# Fujin_Peripherals.net
KiCad netlist of a schematic drawn in Altium Designer
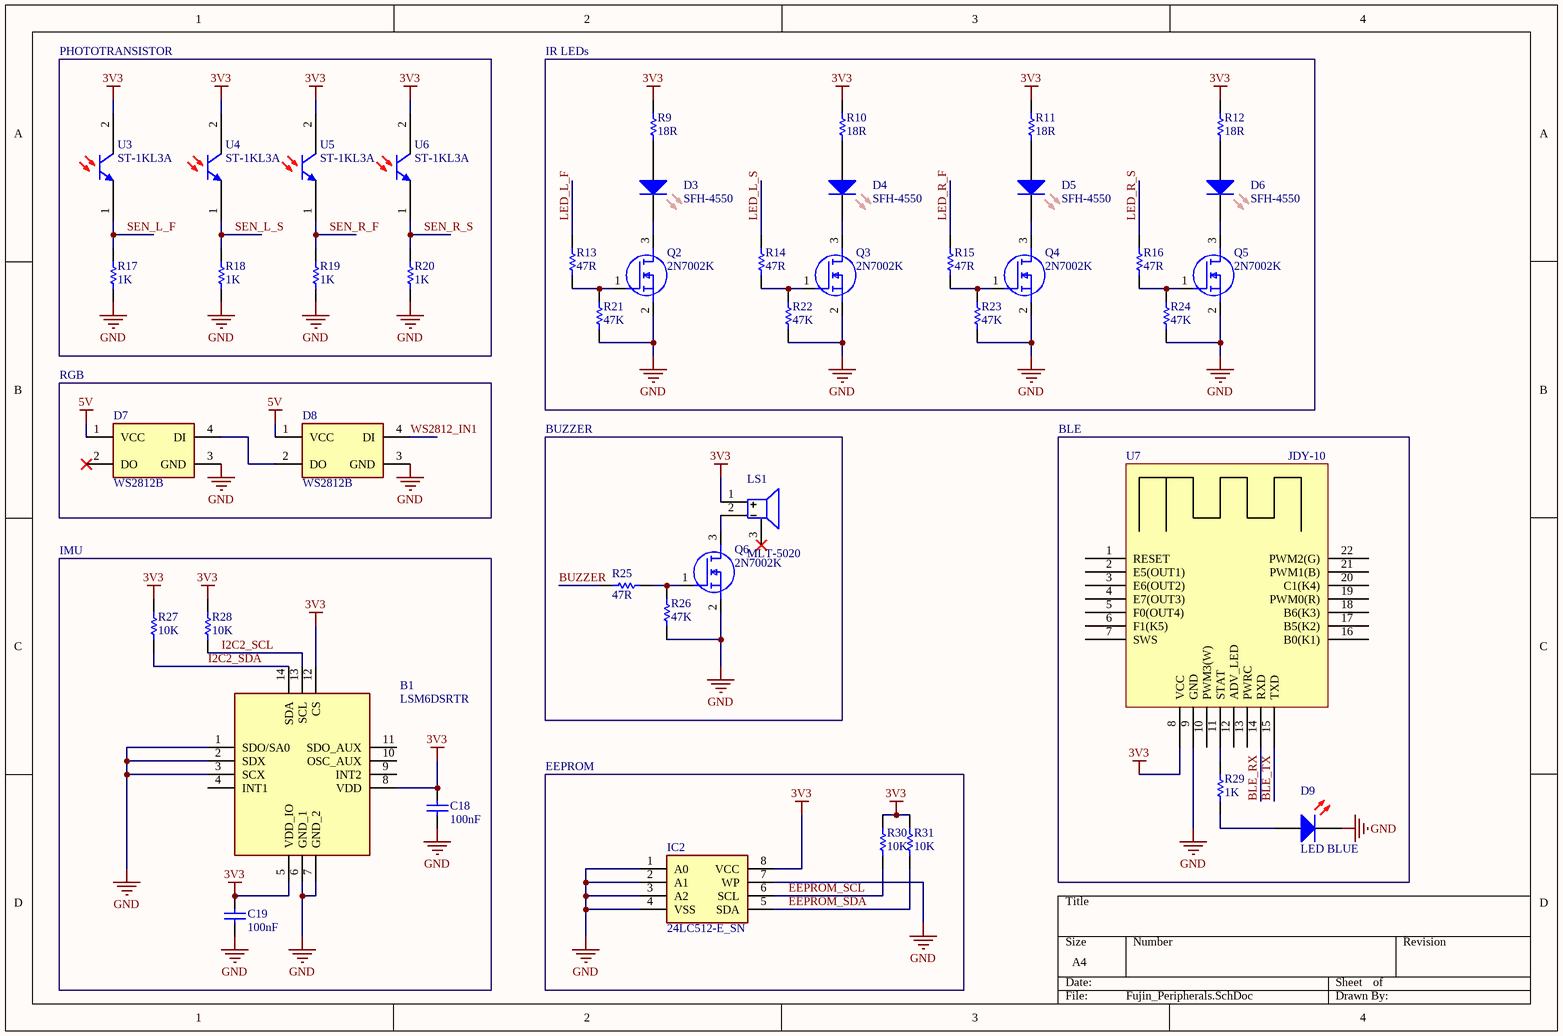
[diagram p0: Fujin_Peripherals.SchDoc]

(export (version "E")
  (design (tool "Eeschema 10.0.6"))
  (components
    (comp (ref "B1")
      (value "LSM6DSRTR")
      (footprint "QFN50P300X250X86-14N")
      (description "IMUs - Inertial Measurement Units")
      (libsource (lib "FujinLib") (part "LSM6DSRTR"))
    )
    (comp (ref "C18")
      (value "100nF")
      (footprint "CAP 0402")
      (description "Capacitor Cer 100nF 50V 0402")
      (fields (field (name "MANUFACTURER PART NUMBER") "IMP14925"))
      (libsource (lib "FujinLib") (part "CAP 100NF 50V 0402"))
    )
    (comp (ref "C19")
      (value "100nF")
      (footprint "CAP 0402")
      (description "Capacitor Cer 100nF 50V 0402")
      (fields (field (name "MANUFACTURER PART NUMBER") "IMP14925"))
      (libsource (lib "FujinLib") (part "CAP 100NF 50V 0402"))
    )
    (comp (ref "D3")
      (value "SFH-4550")
      (footprint "SFH-4550")
      (description "LED 5mm IR")
      (fields (field (name "MANUFACTURER") "OSRAM"))
      (libsource (lib "FujinLib") (part "SFH-4550"))
    )
    (comp (ref "D4")
      (value "SFH-4550")
      (footprint "SFH-4550")
      (description "LED 5mm IR")
      (fields (field (name "MANUFACTURER") "OSRAM"))
      (libsource (lib "FujinLib") (part "SFH-4550"))
    )
    (comp (ref "D5")
      (value "SFH-4550")
      (footprint "SFH-4550")
      (description "LED 5mm IR")
      (fields (field (name "MANUFACTURER") "OSRAM"))
      (libsource (lib "FujinLib") (part "SFH-4550"))
    )
    (comp (ref "D6")
      (value "SFH-4550")
      (footprint "SFH-4550")
      (description "LED 5mm IR")
      (fields (field (name "MANUFACTURER") "OSRAM"))
      (libsource (lib "FujinLib") (part "SFH-4550"))
    )
    (comp (ref "D7")
      (value "WS2812B")
      (footprint "WS2812B")
      (description "Diode")
      (fields (field (name "MANUFACTURER_PART_NUMBER") "WS2812"))
      (libsource (lib "FujinLib") (part "WS2812B"))
    )
    (comp (ref "D8")
      (value "WS2812B")
      (footprint "WS2812B")
      (description "Diode")
      (fields (field (name "MANUFACTURER_PART_NUMBER") "WS2812"))
      (libsource (lib "FujinLib") (part "WS2812B"))
    )
    (comp (ref "D9")
      (value "LED BLUE")
      (footprint "LED 0603")
      (description "LED")
      (fields
        (field (name "MANUFACTURER_PART_NUMBER") "SML-D12U1WT86")
        (field (name "MOUSER PART NUMBER") "755-SML-D12U1WT86")
      )
      (libsource (lib "FujinLib") (part "LED RED 0603"))
    )
    (comp (ref "IC2")
      (value "24LC512-E_SN")
      (footprint "SamacSys:SOIC127P600X175-8N")
      (description "Integrated Circuit")
      (fields
        (field (name "MANUFACTURER_PART_NUMBER") "24LC512-E/SN")
        (field (name "MOUSER PART NUMBER") "579-24LC512-E/SN")
      )
      (libsource (lib "FujinLib") (part "24LC512-E_SN"))
    )
    (comp (ref "LS1")
      (value "MLT-5020")
      (footprint "MLT-5020")
      (description "Loudspeaker or Buzzer")
      (fields
        (field (name "MANUFACTURER_PART_NUMBER") "SMT-0540-S-R")
        (field (name "MOUSER PART NUMBER") "665-SMT0540SR")
      )
      (libsource (lib "FujinLib") (part "MLT-5020"))
    )
    (comp (ref "Q2")
      (value "2N7002K")
      (footprint "SOT95P240X120-3N")
      (description "MOSFET (N-Channel)")
      (fields (field (name "MOUSER PART NUMBER") "512-2N7002K"))
      (libsource (lib "FujinLib") (part "2N7002K"))
    )
    (comp (ref "Q3")
      (value "2N7002K")
      (footprint "SOT95P240X120-3N")
      (description "MOSFET (N-Channel)")
      (fields (field (name "MOUSER PART NUMBER") "512-2N7002K"))
      (libsource (lib "FujinLib") (part "2N7002K"))
    )
    (comp (ref "Q4")
      (value "2N7002K")
      (footprint "SOT95P240X120-3N")
      (description "MOSFET (N-Channel)")
      (fields (field (name "MOUSER PART NUMBER") "512-2N7002K"))
      (libsource (lib "FujinLib") (part "2N7002K"))
    )
    (comp (ref "Q5")
      (value "2N7002K")
      (footprint "SOT95P240X120-3N")
      (description "MOSFET (N-Channel)")
      (fields (field (name "MOUSER PART NUMBER") "512-2N7002K"))
      (libsource (lib "FujinLib") (part "2N7002K"))
    )
    (comp (ref "Q6")
      (value "2N7002K")
      (footprint "SOT95P240X120-3N")
      (description "MOSFET (N-Channel)")
      (fields (field (name "MOUSER PART NUMBER") "512-2N7002K"))
      (libsource (lib "FujinLib") (part "2N7002K"))
    )
    (comp (ref "R9")
      (value "18R")
      (footprint "RESISTOR 0603")
      (fields
        (field (name "MANUFACTURER") "Ty-Ohm")
        (field (name "MANUFACTURER PART NUMBER") "CR25")
        (field (name "TOLERANCE") "±5%")
      )
      (libsource (lib "FujinLib") (part "RES 18R 5%"))
    )
    (comp (ref "R10")
      (value "18R")
      (footprint "RESISTOR 0603")
      (fields
        (field (name "MANUFACTURER") "Ty-Ohm")
        (field (name "MANUFACTURER PART NUMBER") "CR25")
        (field (name "TOLERANCE") "±5%")
      )
      (libsource (lib "FujinLib") (part "RES 18R 5%"))
    )
    (comp (ref "R11")
      (value "18R")
      (footprint "RESISTOR 0603")
      (fields
        (field (name "MANUFACTURER") "Ty-Ohm")
        (field (name "MANUFACTURER PART NUMBER") "CR25")
        (field (name "TOLERANCE") "±5%")
      )
      (libsource (lib "FujinLib") (part "RES 18R 5%"))
    )
    (comp (ref "R12")
      (value "18R")
      (footprint "RESISTOR 0603")
      (fields
        (field (name "MANUFACTURER") "Ty-Ohm")
        (field (name "MANUFACTURER PART NUMBER") "CR25")
        (field (name "TOLERANCE") "±5%")
      )
      (libsource (lib "FujinLib") (part "RES 18R 5%"))
    )
    (comp (ref "R13")
      (value "47R")
      (footprint "RESISTOR 0603")
      (fields
        (field (name "MANUFACTURER") "Ty-Ohm")
        (field (name "MANUFACTURER PART NUMBER") "CR25")
        (field (name "TOLERANCE") "±5%")
      )
      (libsource (lib "FujinLib") (part "RES 47R 5%"))
    )
    (comp (ref "R14")
      (value "47R")
      (footprint "RESISTOR 0603")
      (fields
        (field (name "MANUFACTURER") "Ty-Ohm")
        (field (name "MANUFACTURER PART NUMBER") "CR25")
        (field (name "TOLERANCE") "±5%")
      )
      (libsource (lib "FujinLib") (part "RES 47R 5%"))
    )
    (comp (ref "R15")
      (value "47R")
      (footprint "RESISTOR 0603")
      (fields
        (field (name "MANUFACTURER") "Ty-Ohm")
        (field (name "MANUFACTURER PART NUMBER") "CR25")
        (field (name "TOLERANCE") "±5%")
      )
      (libsource (lib "FujinLib") (part "RES 47R 5%"))
    )
    (comp (ref "R16")
      (value "47R")
      (footprint "RESISTOR 0603")
      (fields
        (field (name "MANUFACTURER") "Ty-Ohm")
        (field (name "MANUFACTURER PART NUMBER") "CR25")
        (field (name "TOLERANCE") "±5%")
      )
      (libsource (lib "FujinLib") (part "RES 47R 5%"))
    )
    (comp (ref "R17")
      (value "1K")
      (footprint "RESISTOR 0603")
      (fields
        (field (name "MANUFACTURER") "Ty-Ohm")
        (field (name "MANUFACTURER PART NUMBER") "CR25")
        (field (name "TOLERANCE") "±5%")
      )
      (libsource (lib "FujinLib") (part "RES 1K 5%"))
    )
    (comp (ref "R18")
      (value "1K")
      (footprint "RESISTOR 0603")
      (fields
        (field (name "MANUFACTURER") "Ty-Ohm")
        (field (name "MANUFACTURER PART NUMBER") "CR25")
        (field (name "TOLERANCE") "±5%")
      )
      (libsource (lib "FujinLib") (part "RES 1K 5%"))
    )
    (comp (ref "R19")
      (value "1K")
      (footprint "RESISTOR 0603")
      (fields
        (field (name "MANUFACTURER") "Ty-Ohm")
        (field (name "MANUFACTURER PART NUMBER") "CR25")
        (field (name "TOLERANCE") "±5%")
      )
      (libsource (lib "FujinLib") (part "RES 1K 5%"))
    )
    (comp (ref "R20")
      (value "1K")
      (footprint "RESISTOR 0603")
      (fields
        (field (name "MANUFACTURER") "Ty-Ohm")
        (field (name "MANUFACTURER PART NUMBER") "CR25")
        (field (name "TOLERANCE") "±5%")
      )
      (libsource (lib "FujinLib") (part "RES 1K 5%"))
    )
    (comp (ref "R21")
      (value "47K")
      (footprint "RESISTOR 0603")
      (fields
        (field (name "MANUFACTURER") "Ty-Ohm")
        (field (name "MANUFACTURER PART NUMBER") "CR25")
        (field (name "TOLERANCE") "±5%")
      )
      (libsource (lib "FujinLib") (part "RES 47K 5%"))
    )
    (comp (ref "R22")
      (value "47K")
      (footprint "RESISTOR 0603")
      (fields
        (field (name "MANUFACTURER") "Ty-Ohm")
        (field (name "MANUFACTURER PART NUMBER") "CR25")
        (field (name "TOLERANCE") "±5%")
      )
      (libsource (lib "FujinLib") (part "RES 47K 5%"))
    )
    (comp (ref "R23")
      (value "47K")
      (footprint "RESISTOR 0603")
      (fields
        (field (name "MANUFACTURER") "Ty-Ohm")
        (field (name "MANUFACTURER PART NUMBER") "CR25")
        (field (name "TOLERANCE") "±5%")
      )
      (libsource (lib "FujinLib") (part "RES 47K 5%"))
    )
    (comp (ref "R24")
      (value "47K")
      (footprint "RESISTOR 0603")
      (fields
        (field (name "MANUFACTURER") "Ty-Ohm")
        (field (name "MANUFACTURER PART NUMBER") "CR25")
        (field (name "TOLERANCE") "±5%")
      )
      (libsource (lib "FujinLib") (part "RES 47K 5%"))
    )
    (comp (ref "R25")
      (value "47R")
      (footprint "RESISTOR 0603")
      (fields
        (field (name "MANUFACTURER") "Ty-Ohm")
        (field (name "MANUFACTURER PART NUMBER") "CR25")
        (field (name "TOLERANCE") "±5%")
      )
      (libsource (lib "FujinLib") (part "RES 47R 5%"))
    )
    (comp (ref "R26")
      (value "47K")
      (footprint "RESISTOR 0603")
      (fields
        (field (name "MANUFACTURER") "Ty-Ohm")
        (field (name "MANUFACTURER PART NUMBER") "CR25")
        (field (name "TOLERANCE") "±5%")
      )
      (libsource (lib "FujinLib") (part "RES 47K 5%"))
    )
    (comp (ref "R27")
      (value "10K")
      (footprint "RESISTOR 0402")
      (fields
        (field (name "MANUFACTURER") "PANASONIC ELECTRONIC COMPONENTS")
        (field (name "MANUFACTURER PART NUMBER") "ERJ-3GEYJ103V")
        (field (name "TOLERANCE") "±5%")
      )
      (libsource (lib "FujinLib") (part "RES 10K 5%"))
    )
    (comp (ref "R28")
      (value "10K")
      (footprint "RESISTOR 0402")
      (fields
        (field (name "MANUFACTURER") "PANASONIC ELECTRONIC COMPONENTS")
        (field (name "MANUFACTURER PART NUMBER") "ERJ-3GEYJ103V")
        (field (name "TOLERANCE") "±5%")
      )
      (libsource (lib "FujinLib") (part "RES 10K 5%"))
    )
    (comp (ref "R29")
      (value "1K")
      (footprint "RESISTOR 0603")
      (fields
        (field (name "MANUFACTURER") "Ty-Ohm")
        (field (name "MANUFACTURER PART NUMBER") "CR25")
        (field (name "TOLERANCE") "±5%")
      )
      (libsource (lib "FujinLib") (part "RES 1K 5%"))
    )
    (comp (ref "R30")
      (value "10K")
      (footprint "RESISTOR 0402")
      (fields
        (field (name "MANUFACTURER") "PANASONIC ELECTRONIC COMPONENTS")
        (field (name "MANUFACTURER PART NUMBER") "ERJ-3GEYJ103V")
        (field (name "TOLERANCE") "±5%")
      )
      (libsource (lib "FujinLib") (part "RES 10K 5%"))
    )
    (comp (ref "R31")
      (value "10K")
      (footprint "RESISTOR 0402")
      (fields
        (field (name "MANUFACTURER") "PANASONIC ELECTRONIC COMPONENTS")
        (field (name "MANUFACTURER PART NUMBER") "ERJ-3GEYJ103V")
        (field (name "TOLERANCE") "±5%")
      )
      (libsource (lib "FujinLib") (part "RES 10K 5%"))
    )
    (comp (ref "U3")
      (value "ST-1KL3A")
      (footprint "ST-1KL3A")
      (description "Phototransistor")
      (libsource (lib "FujinLib") (part "ST-1KL3A"))
    )
    (comp (ref "U4")
      (value "ST-1KL3A")
      (footprint "ST-1KL3A")
      (description "Phototransistor")
      (libsource (lib "FujinLib") (part "ST-1KL3A"))
    )
    (comp (ref "U5")
      (value "ST-1KL3A")
      (footprint "ST-1KL3A")
      (description "Phototransistor")
      (libsource (lib "FujinLib") (part "ST-1KL3A"))
    )
    (comp (ref "U6")
      (value "ST-1KL3A")
      (footprint "ST-1KL3A")
      (description "Phototransistor")
      (libsource (lib "FujinLib") (part "ST-1KL3A"))
    )
    (comp (ref "U7")
      (value "JDY-10")
      (footprint "JDY-10 - Half")
      (libsource (lib "FujinLib") (part "JDY-10-Bluetooth"))
    )
  )
  (nets
    (net (code "1") (name "/BLE_RX") (class "Default")
      (node (ref "U7") (pin "14") (pinfunction "RXD_14") (pintype "passive"))
    )
    (net (code "2") (name "/BLE_TX") (class "Default")
      (node (ref "U7") (pin "15") (pinfunction "TXD_15") (pintype "passive"))
    )
    (net (code "3") (name "/BUZZER") (class "Default")
      (node (ref "R25") (pin "1") (pinfunction "1_1") (pintype "passive"))
    )
    (net (code "4") (name "/EEPROM_SCL") (class "Default")
      (node (ref "IC2") (pin "6") (pinfunction "SCL_6") (pintype "passive"))
      (node (ref "R30") (pin "1") (pinfunction "1_1") (pintype "passive"))
    )
    (net (code "5") (name "/EEPROM_SDA") (class "Default")
      (node (ref "IC2") (pin "5") (pinfunction "SDA_5") (pintype "passive"))
      (node (ref "R31") (pin "1") (pinfunction "1_1") (pintype "passive"))
    )
    (net (code "6") (name "/I2C2_SCL") (class "Default")
      (node (ref "B1") (pin "13") (pinfunction "SCL_13") (pintype "passive"))
      (node (ref "R28") (pin "1") (pinfunction "1_1") (pintype "passive"))
    )
    (net (code "7") (name "/I2C2_SDA") (class "Default")
      (node (ref "B1") (pin "14") (pinfunction "SDA_14") (pintype "passive"))
      (node (ref "R27") (pin "1") (pinfunction "1_1") (pintype "passive"))
    )
    (net (code "8") (name "/LED_L_F") (class "Default")
      (node (ref "R13") (pin "2") (pinfunction "2_2") (pintype "passive"))
    )
    (net (code "9") (name "/LED_L_S") (class "Default")
      (node (ref "R14") (pin "2") (pinfunction "2_2") (pintype "passive"))
    )
    (net (code "10") (name "/LED_R_F") (class "Default")
      (node (ref "R15") (pin "2") (pinfunction "2_2") (pintype "passive"))
    )
    (net (code "11") (name "/LED_R_S") (class "Default")
      (node (ref "R16") (pin "2") (pinfunction "2_2") (pintype "passive"))
    )
    (net (code "12") (name "/SEN_L_F") (class "Default")
      (node (ref "R17") (pin "2") (pinfunction "2_2") (pintype "passive"))
      (node (ref "U3") (pin "1") (pinfunction "EMITTER_1") (pintype "passive"))
    )
    (net (code "13") (name "/SEN_L_S") (class "Default")
      (node (ref "R18") (pin "2") (pinfunction "2_2") (pintype "passive"))
      (node (ref "U4") (pin "1") (pinfunction "EMITTER_1") (pintype "passive"))
    )
    (net (code "14") (name "/SEN_R_F") (class "Default")
      (node (ref "R19") (pin "2") (pinfunction "2_2") (pintype "passive"))
      (node (ref "U5") (pin "1") (pinfunction "EMITTER_1") (pintype "passive"))
    )
    (net (code "15") (name "/SEN_R_S") (class "Default")
      (node (ref "R20") (pin "2") (pinfunction "2_2") (pintype "passive"))
      (node (ref "U6") (pin "1") (pinfunction "EMITTER_1") (pintype "passive"))
    )
    (net (code "16") (name "/WS2812_IN1") (class "Default")
      (node (ref "D8") (pin "4") (pinfunction "DI_4") (pintype "passive"))
    )
    (net (code "17") (name "3V3") (class "Default")
      (node (ref "B1") (pin "12") (pinfunction "CS_12") (pintype "passive"))
      (node (ref "B1") (pin "5") (pinfunction "VDD_IO_5") (pintype "power_in"))
      (node (ref "B1") (pin "8") (pinfunction "VDD_8") (pintype "power_in"))
      (node (ref "C18") (pin "2") (pinfunction "2_2") (pintype "passive"))
      (node (ref "C19") (pin "2") (pinfunction "2_2") (pintype "passive"))
      (node (ref "IC2") (pin "8") (pinfunction "VCC_8") (pintype "passive"))
      (node (ref "LS1") (pin "1") (pinfunction "+_1") (pintype "passive"))
      (node (ref "R10") (pin "2") (pinfunction "2_2") (pintype "passive"))
      (node (ref "R11") (pin "2") (pinfunction "2_2") (pintype "passive"))
      (node (ref "R12") (pin "2") (pinfunction "2_2") (pintype "passive"))
      (node (ref "R27") (pin "2") (pinfunction "2_2") (pintype "passive"))
      (node (ref "R28") (pin "2") (pinfunction "2_2") (pintype "passive"))
      (node (ref "R30") (pin "2") (pinfunction "2_2") (pintype "passive"))
      (node (ref "R31") (pin "2") (pinfunction "2_2") (pintype "passive"))
      (node (ref "R9") (pin "2") (pinfunction "2_2") (pintype "passive"))
      (node (ref "U3") (pin "2") (pinfunction "COLLECTOR_2") (pintype "passive"))
      (node (ref "U4") (pin "2") (pinfunction "COLLECTOR_2") (pintype "passive"))
      (node (ref "U5") (pin "2") (pinfunction "COLLECTOR_2") (pintype "passive"))
      (node (ref "U6") (pin "2") (pinfunction "COLLECTOR_2") (pintype "passive"))
      (node (ref "U7") (pin "8") (pinfunction "VCC_8") (pintype "power_in"))
    )
    (net (code "18") (name "5V") (class "Default")
      (node (ref "D7") (pin "1") (pinfunction "VCC_1") (pintype "power_in"))
      (node (ref "D8") (pin "1") (pinfunction "VCC_1") (pintype "power_in"))
    )
    (net (code "19") (name "GND") (class "Default")
      (node (ref "B1") (pin "1") (pinfunction "SDO/SA0_1") (pintype "passive"))
      (node (ref "B1") (pin "2") (pinfunction "SDX_2") (pintype "passive"))
      (node (ref "B1") (pin "3") (pinfunction "SCX_3") (pintype "passive"))
      (node (ref "B1") (pin "6") (pinfunction "GND_1_6") (pintype "passive"))
      (node (ref "B1") (pin "7") (pinfunction "GND_2_7") (pintype "passive"))
      (node (ref "C18") (pin "1") (pinfunction "1_1") (pintype "passive"))
      (node (ref "C19") (pin "1") (pinfunction "1_1") (pintype "passive"))
      (node (ref "D7") (pin "3") (pinfunction "GND_3") (pintype "power_in"))
      (node (ref "D8") (pin "3") (pinfunction "GND_3") (pintype "power_in"))
      (node (ref "D9") (pin "2") (pinfunction "K_2") (pintype "passive"))
      (node (ref "IC2") (pin "1") (pinfunction "A0_1") (pintype "passive"))
      (node (ref "IC2") (pin "2") (pinfunction "A1_2") (pintype "passive"))
      (node (ref "IC2") (pin "3") (pinfunction "A2_3") (pintype "passive"))
      (node (ref "IC2") (pin "4") (pinfunction "VSS_4") (pintype "passive"))
      (node (ref "IC2") (pin "7") (pinfunction "WP_7") (pintype "passive"))
      (node (ref "Q2") (pin "2") (pinfunction "S_2") (pintype "passive"))
      (node (ref "Q3") (pin "2") (pinfunction "S_2") (pintype "passive"))
      (node (ref "Q4") (pin "2") (pinfunction "S_2") (pintype "passive"))
      (node (ref "Q5") (pin "2") (pinfunction "S_2") (pintype "passive"))
      (node (ref "Q6") (pin "2") (pinfunction "S_2") (pintype "passive"))
      (node (ref "R17") (pin "1") (pinfunction "1_1") (pintype "passive"))
      (node (ref "R18") (pin "1") (pinfunction "1_1") (pintype "passive"))
      (node (ref "R19") (pin "1") (pinfunction "1_1") (pintype "passive"))
      (node (ref "R20") (pin "1") (pinfunction "1_1") (pintype "passive"))
      (node (ref "R21") (pin "1") (pinfunction "1_1") (pintype "passive"))
      (node (ref "R22") (pin "1") (pinfunction "1_1") (pintype "passive"))
      (node (ref "R23") (pin "1") (pinfunction "1_1") (pintype "passive"))
      (node (ref "R24") (pin "1") (pinfunction "1_1") (pintype "passive"))
      (node (ref "R26") (pin "1") (pinfunction "1_1") (pintype "passive"))
      (node (ref "U7") (pin "9") (pinfunction "GND_9") (pintype "power_in"))
    )
    (net (code "20") (name "Net-(D3-A)") (class "Default")
      (node (ref "D3") (pin "1") (pinfunction "A_1") (pintype "passive"))
      (node (ref "R9") (pin "1") (pinfunction "1_1") (pintype "passive"))
    )
    (net (code "21") (name "Net-(D3-K)") (class "Default")
      (node (ref "D3") (pin "2") (pinfunction "K_2") (pintype "passive"))
      (node (ref "Q2") (pin "3") (pinfunction "D_3") (pintype "passive"))
    )
    (net (code "22") (name "Net-(D4-A)") (class "Default")
      (node (ref "D4") (pin "1") (pinfunction "A_1") (pintype "passive"))
      (node (ref "R10") (pin "1") (pinfunction "1_1") (pintype "passive"))
    )
    (net (code "23") (name "Net-(D4-K)") (class "Default")
      (node (ref "D4") (pin "2") (pinfunction "K_2") (pintype "passive"))
      (node (ref "Q3") (pin "3") (pinfunction "D_3") (pintype "passive"))
    )
    (net (code "24") (name "Net-(D5-A)") (class "Default")
      (node (ref "D5") (pin "1") (pinfunction "A_1") (pintype "passive"))
      (node (ref "R11") (pin "1") (pinfunction "1_1") (pintype "passive"))
    )
    (net (code "25") (name "Net-(D5-K)") (class "Default")
      (node (ref "D5") (pin "2") (pinfunction "K_2") (pintype "passive"))
      (node (ref "Q4") (pin "3") (pinfunction "D_3") (pintype "passive"))
    )
    (net (code "26") (name "Net-(D6-A)") (class "Default")
      (node (ref "D6") (pin "1") (pinfunction "A_1") (pintype "passive"))
      (node (ref "R12") (pin "1") (pinfunction "1_1") (pintype "passive"))
    )
    (net (code "27") (name "Net-(D6-K)") (class "Default")
      (node (ref "D6") (pin "2") (pinfunction "K_2") (pintype "passive"))
      (node (ref "Q5") (pin "3") (pinfunction "D_3") (pintype "passive"))
    )
    (net (code "28") (name "Net-(D7-DI)") (class "Default")
      (node (ref "D7") (pin "4") (pinfunction "DI_4") (pintype "passive"))
      (node (ref "D8") (pin "2") (pinfunction "DO_2") (pintype "passive"))
    )
    (net (code "29") (name "Net-(D9-A)") (class "Default")
      (node (ref "D9") (pin "1") (pinfunction "A_1") (pintype "passive"))
      (node (ref "R29") (pin "1") (pinfunction "1_1") (pintype "passive"))
    )
    (net (code "30") (name "Net-(LS1--)") (class "Default")
      (node (ref "LS1") (pin "2") (pinfunction "-_2") (pintype "passive"))
      (node (ref "Q6") (pin "3") (pinfunction "D_3") (pintype "passive"))
    )
    (net (code "31") (name "Net-(Q2-G)") (class "Default")
      (node (ref "Q2") (pin "1") (pinfunction "G_1") (pintype "passive"))
      (node (ref "R13") (pin "1") (pinfunction "1_1") (pintype "passive"))
      (node (ref "R21") (pin "2") (pinfunction "2_2") (pintype "passive"))
    )
    (net (code "32") (name "Net-(Q3-G)") (class "Default")
      (node (ref "Q3") (pin "1") (pinfunction "G_1") (pintype "passive"))
      (node (ref "R14") (pin "1") (pinfunction "1_1") (pintype "passive"))
      (node (ref "R22") (pin "2") (pinfunction "2_2") (pintype "passive"))
    )
    (net (code "33") (name "Net-(Q4-G)") (class "Default")
      (node (ref "Q4") (pin "1") (pinfunction "G_1") (pintype "passive"))
      (node (ref "R15") (pin "1") (pinfunction "1_1") (pintype "passive"))
      (node (ref "R23") (pin "2") (pinfunction "2_2") (pintype "passive"))
    )
    (net (code "34") (name "Net-(Q5-G)") (class "Default")
      (node (ref "Q5") (pin "1") (pinfunction "G_1") (pintype "passive"))
      (node (ref "R16") (pin "1") (pinfunction "1_1") (pintype "passive"))
      (node (ref "R24") (pin "2") (pinfunction "2_2") (pintype "passive"))
    )
    (net (code "35") (name "Net-(Q6-G)") (class "Default")
      (node (ref "Q6") (pin "1") (pinfunction "G_1") (pintype "passive"))
      (node (ref "R25") (pin "2") (pinfunction "2_2") (pintype "passive"))
      (node (ref "R26") (pin "2") (pinfunction "2_2") (pintype "passive"))
    )
    (net (code "36") (name "Net-(U7-STAT)") (class "Default")
      (node (ref "R29") (pin "2") (pinfunction "2_2") (pintype "passive"))
      (node (ref "U7") (pin "11") (pinfunction "STAT_11") (pintype "passive"))
    )
    (net (code "37") (name "unconnected-(B1-INT1-Pad4)") (class "Default")
      (node (ref "B1") (pin "4") (pinfunction "INT1_4") (pintype "passive"))
    )
    (net (code "38") (name "unconnected-(B1-INT2-Pad9)") (class "Default")
      (node (ref "B1") (pin "9") (pinfunction "INT2_9") (pintype "passive"))
    )
    (net (code "39") (name "unconnected-(B1-OSC_AUX-Pad10)") (class "Default")
      (node (ref "B1") (pin "10") (pinfunction "OSC_AUX_10") (pintype "passive"))
    )
    (net (code "40") (name "unconnected-(B1-SDO_AUX-Pad11)") (class "Default")
      (node (ref "B1") (pin "11") (pinfunction "SDO_AUX_11") (pintype "passive"))
    )
    (net (code "41") (name "unconnected-(D7-DO-Pad2)") (class "Default")
      (node (ref "D7") (pin "2") (pinfunction "DO_2") (pintype "passive+no_connect"))
    )
    (net (code "42") (name "unconnected-(LS1-DUMMY-Pad3)") (class "Default")
      (node (ref "LS1") (pin "3") (pinfunction "DUMMY_3") (pintype "passive+no_connect"))
    )
    (net (code "43") (name "unconnected-(U7-ADV_LED-Pad12)") (class "Default")
      (node (ref "U7") (pin "12") (pinfunction "ADV_LED_12") (pintype "passive"))
    )
    (net (code "44") (name "unconnected-(U7-B0(K1)-Pad16)") (class "Default")
      (node (ref "U7") (pin "16") (pinfunction "B0(K1)_16") (pintype "passive"))
    )
    (net (code "45") (name "unconnected-(U7-B5(K2)-Pad17)") (class "Default")
      (node (ref "U7") (pin "17") (pinfunction "B5(K2)_17") (pintype "passive"))
    )
    (net (code "46") (name "unconnected-(U7-B6(K3)-Pad18)") (class "Default")
      (node (ref "U7") (pin "18") (pinfunction "B6(K3)_18") (pintype "passive"))
    )
    (net (code "47") (name "unconnected-(U7-C1(K4)-Pad20)") (class "Default")
      (node (ref "U7") (pin "20") (pinfunction "C1(K4)_20") (pintype "passive"))
    )
    (net (code "48") (name "unconnected-(U7-E5(OUT1)-Pad2)") (class "Default")
      (node (ref "U7") (pin "2") (pinfunction "E5(OUT1)_2") (pintype "passive"))
    )
    (net (code "49") (name "unconnected-(U7-E6(OUT2)-Pad3)") (class "Default")
      (node (ref "U7") (pin "3") (pinfunction "E6(OUT2)_3") (pintype "passive"))
    )
    (net (code "50") (name "unconnected-(U7-E7(OUT3)-Pad4)") (class "Default")
      (node (ref "U7") (pin "4") (pinfunction "E7(OUT3)_4") (pintype "passive"))
    )
    (net (code "51") (name "unconnected-(U7-F0(OUT4)-Pad5)") (class "Default")
      (node (ref "U7") (pin "5") (pinfunction "F0(OUT4)_5") (pintype "passive"))
    )
    (net (code "52") (name "unconnected-(U7-F1(K5)-Pad6)") (class "Default")
      (node (ref "U7") (pin "6") (pinfunction "F1(K5)_6") (pintype "passive"))
    )
    (net (code "53") (name "unconnected-(U7-PWM0(R)-Pad19)") (class "Default")
      (node (ref "U7") (pin "19") (pinfunction "PWM0(R)_19") (pintype "passive"))
    )
    (net (code "54") (name "unconnected-(U7-PWM1(B)-Pad21)") (class "Default")
      (node (ref "U7") (pin "21") (pinfunction "PWM1(B)_21") (pintype "passive"))
    )
    (net (code "55") (name "unconnected-(U7-PWM2(G)-Pad22)") (class "Default")
      (node (ref "U7") (pin "22") (pinfunction "PWM2(G)_22") (pintype "passive"))
    )
    (net (code "56") (name "unconnected-(U7-PWM3(W)-Pad10)") (class "Default")
      (node (ref "U7") (pin "10") (pinfunction "PWM3(W)_10") (pintype "passive"))
    )
    (net (code "57") (name "unconnected-(U7-PWRC-Pad13)") (class "Default")
      (node (ref "U7") (pin "13") (pinfunction "PWRC_13") (pintype "passive"))
    )
    (net (code "58") (name "unconnected-(U7-RESET-Pad1)") (class "Default")
      (node (ref "U7") (pin "1") (pinfunction "RESET_1") (pintype "passive"))
    )
    (net (code "59") (name "unconnected-(U7-SWS-Pad7)") (class "Default")
      (node (ref "U7") (pin "7") (pinfunction "SWS_7") (pintype "passive"))
    )
  )
)
